# RS232_IrDA.net
KiCad netlist of a schematic drawn in Altium Designer
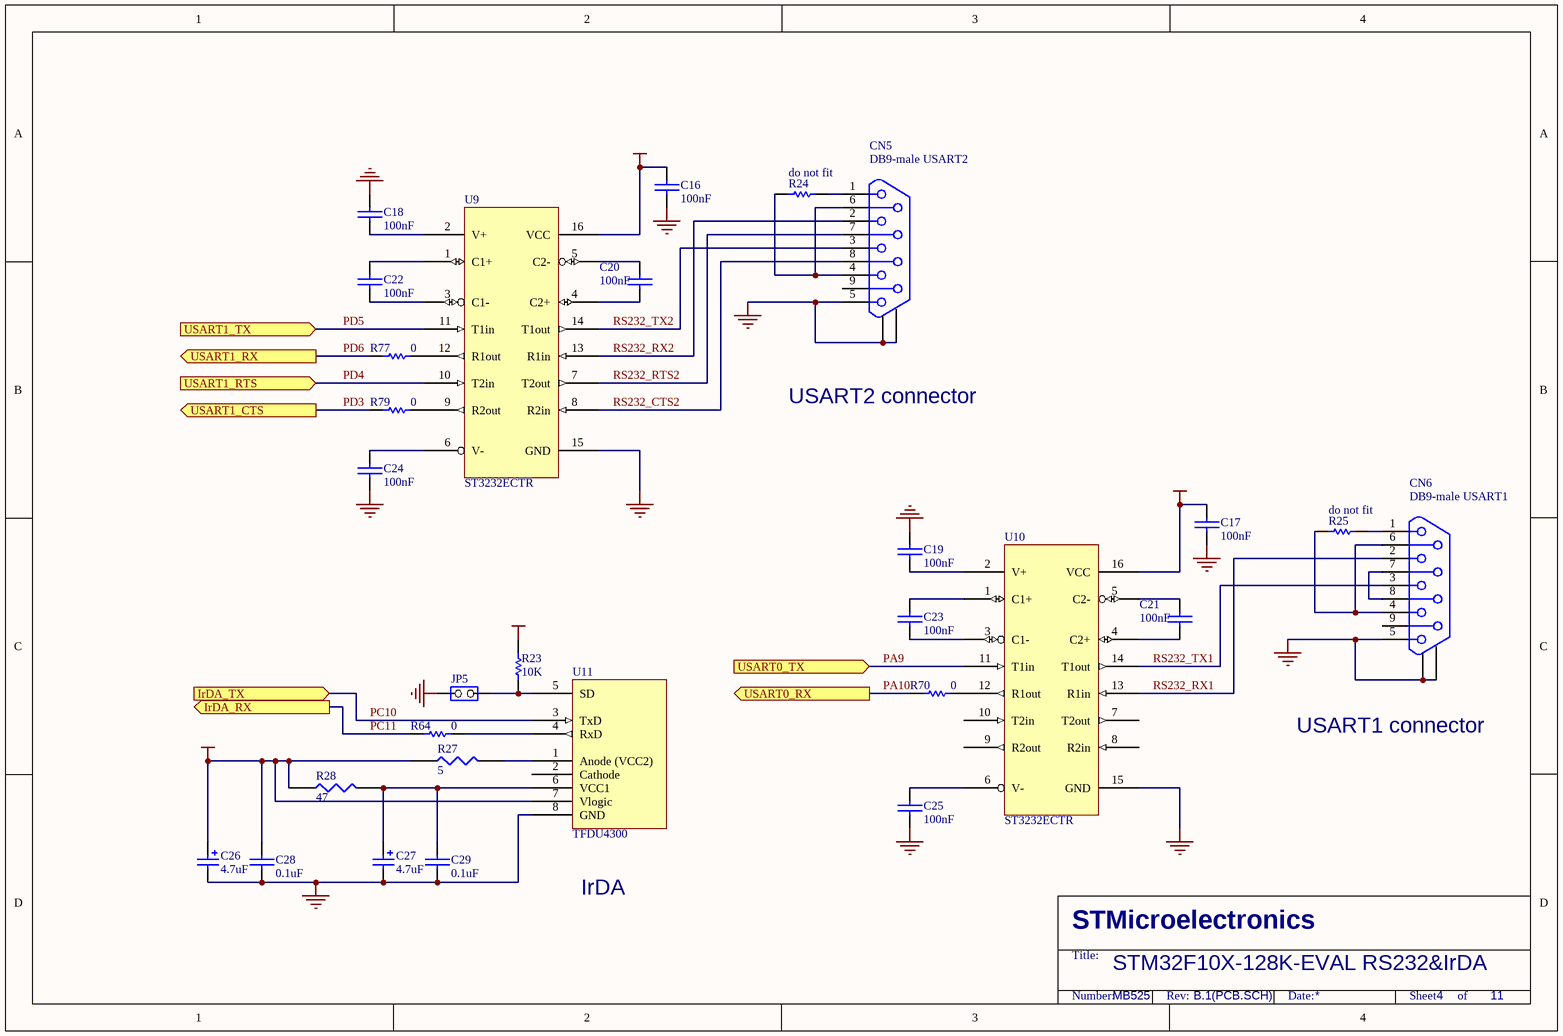
[diagram p0: RS232&IrDA.SchDoc]

(export (version "E")
  (design (tool "Eeschema 10.0.6"))
  (components
    (comp (ref "C16")
      (value "100nF")
      (footprint "0603P")
      (description "Capacitor")
      (libsource (lib "*") (part "CAP"))
    )
    (comp (ref "C17")
      (value "100nF")
      (footprint "0603P")
      (description "Capacitor")
      (libsource (lib "*") (part "CAP"))
    )
    (comp (ref "C18")
      (value "100nF")
      (footprint "0603P")
      (description "Capacitor")
      (libsource (lib "*") (part "CAP"))
    )
    (comp (ref "C19")
      (value "100nF")
      (footprint "0603P")
      (description "Capacitor")
      (libsource (lib "*") (part "CAP"))
    )
    (comp (ref "C20")
      (value "100nF")
      (footprint "0603P")
      (description "Capacitor")
      (libsource (lib "*") (part "CAP"))
    )
    (comp (ref "C21")
      (value "100nF")
      (footprint "0603P")
      (description "Capacitor")
      (libsource (lib "*") (part "CAP"))
    )
    (comp (ref "C22")
      (value "100nF")
      (footprint "0603P")
      (description "Capacitor")
      (libsource (lib "*") (part "CAP"))
    )
    (comp (ref "C23")
      (value "100nF")
      (footprint "0603P")
      (description "Capacitor")
      (libsource (lib "*") (part "CAP"))
    )
    (comp (ref "C24")
      (value "100nF")
      (footprint "0603P")
      (description "Capacitor")
      (libsource (lib "*") (part "CAP"))
    )
    (comp (ref "C25")
      (value "100nF")
      (footprint "0603P")
      (description "Capacitor")
      (libsource (lib "*") (part "CAP"))
    )
    (comp (ref "C26")
      (value "4.7uF")
      (footprint "TAN-B")
      (description "Polarized Capacitor (Radial)")
      (fields (field (name "PUBLISHER") "Altium Limited"))
      (libsource (lib "Miscellaneous Devices") (part "Cap Pol1"))
    )
    (comp (ref "C27")
      (value "4.7uF")
      (footprint "TAN-B")
      (description "Polarized Capacitor (Radial)")
      (fields (field (name "PUBLISHER") "Altium Limited"))
      (libsource (lib "Miscellaneous Devices") (part "Cap Pol1"))
    )
    (comp (ref "C28")
      (value "0.1uF")
      (footprint "0603P")
      (description "Capacitor")
      (libsource (lib "*") (part "CAP"))
    )
    (comp (ref "C29")
      (value "0.1uF")
      (footprint "0603P")
      (description "Capacitor")
      (libsource (lib "*") (part "CAP"))
    )
    (comp (ref "CN5") (value "DB9-male USART2") (footprint "DB9/M") (libsource (lib "*") (part "DB9")))
    (comp (ref "CN6") (value "DB9-male USART1") (footprint "DB9/M") (libsource (lib "*") (part "DB9")))
    (comp (ref "JP5") (value "~") (footprint "SIP2") (libsource (lib "*") (part "JP2")))
    (comp (ref "R23")
      (value "10K")
      (description "Resistor")
      (fields (field (name "PUBLISHER") "Altium Limited"))
      (libsource (lib "Miscellaneous Devices") (part "Res1"))
    )
    (comp (ref "R24")
      (value "do not fit")
      (footprint "0603_NC")
      (description "Resistor")
      (fields (field (name "PUBLISHER") "Altium Limited"))
      (libsource (lib "Miscellaneous Devices") (part "res1"))
    )
    (comp (ref "R25")
      (value "do not fit")
      (footprint "0603_NC")
      (description "Resistor")
      (fields (field (name "PUBLISHER") "Altium Limited"))
      (libsource (lib "Miscellaneous Devices") (part "res1"))
    )
    (comp (ref "R27") (value "5") (footprint "0603") (libsource (lib "*") (part "RES1")))
    (comp (ref "R28") (value "47") (footprint "0603") (libsource (lib "*") (part "RES1")))
    (comp (ref "R64")
      (value "0")
      (description "Resistor")
      (fields (field (name "PUBLISHER") "Altium Limited"))
      (libsource (lib "Miscellaneous Devices") (part "Res1"))
    )
    (comp (ref "R70")
      (value "0")
      (description "Resistor")
      (fields (field (name "PUBLISHER") "Altium Limited"))
      (libsource (lib "Miscellaneous Devices") (part "Res1"))
    )
    (comp (ref "R77")
      (value "0")
      (description "Resistor")
      (fields (field (name "PUBLISHER") "Altium Limited"))
      (libsource (lib "Miscellaneous Devices") (part "Res1"))
    )
    (comp (ref "R79")
      (value "0")
      (description "Resistor")
      (fields (field (name "PUBLISHER") "Altium Limited"))
      (libsource (lib "Miscellaneous Devices") (part "Res1"))
    )
    (comp (ref "U9")
      (value "ST3232ECTR")
      (footprint "TSSOP16")
      (description "3.3V/5V Dual RS232 Transceiver w/ Int. Cap.")
      (libsource (lib "*") (part "ST3232"))
    )
    (comp (ref "U10")
      (value "ST3232ECTR")
      (footprint "TSSOP16")
      (description "3.3V/5V Dual RS232 Transceiver w/ Int. Cap.")
      (libsource (lib "*") (part "ST3232"))
    )
    (comp (ref "U11") (value "TFDU4300") (footprint "IR_VISHAY3") (libsource (lib "*") (part "TFDU4300")))
  )
  (nets
    (net (code "1") (name "+3V3") (class "Default")
      (node (ref "C16") (pin "1") (pinfunction "1_1") (pintype "passive"))
      (node (ref "C17") (pin "1") (pinfunction "1_1") (pintype "passive"))
      (node (ref "C26") (pin "1") (pinfunction "1_1") (pintype "passive"))
      (node (ref "C28") (pin "1") (pinfunction "1_1") (pintype "passive"))
      (node (ref "R23") (pin "2") (pinfunction "2_2") (pintype "passive"))
      (node (ref "R27") (pin "1") (pinfunction "1_1") (pintype "passive"))
      (node (ref "R28") (pin "1") (pinfunction "1_1") (pintype "passive"))
      (node (ref "U10") (pin "16") (pinfunction "VCC_16") (pintype "passive"))
      (node (ref "U11") (pin "7") (pinfunction "Vlogic_7") (pintype "passive"))
      (node (ref "U9") (pin "16") (pinfunction "VCC_16") (pintype "passive"))
    )
    (net (code "2") (name "/PA9") (class "Default")
      (node (ref "U10") (pin "11") (pinfunction "T1in_11") (pintype "input"))
    )
    (net (code "3") (name "/PA10") (class "Default")
      (node (ref "R70") (pin "2") (pinfunction "2_2") (pintype "passive"))
    )
    (net (code "4") (name "/PC10") (class "Default")
      (node (ref "U11") (pin "3") (pinfunction "TxD_3") (pintype "input"))
    )
    (net (code "5") (name "/PC11") (class "Default")
      (node (ref "R64") (pin "2") (pinfunction "2_2") (pintype "passive"))
    )
    (net (code "6") (name "/PD3") (class "Default")
      (node (ref "R79") (pin "2") (pinfunction "2_2") (pintype "passive"))
    )
    (net (code "7") (name "/PD4") (class "Default")
      (node (ref "U9") (pin "10") (pinfunction "T2in_10") (pintype "input"))
    )
    (net (code "8") (name "/PD5") (class "Default")
      (node (ref "U9") (pin "11") (pinfunction "T1in_11") (pintype "input"))
    )
    (net (code "9") (name "/PD6") (class "Default")
      (node (ref "R77") (pin "2") (pinfunction "2_2") (pintype "passive"))
    )
    (net (code "10") (name "/RS232_CTS2") (class "Default")
      (node (ref "CN5") (pin "8") (pinfunction "8_8") (pintype "passive"))
      (node (ref "U9") (pin "8") (pinfunction "R2in_8") (pintype "input"))
    )
    (net (code "11") (name "/RS232_RTS2") (class "Default")
      (node (ref "CN5") (pin "7") (pinfunction "7_7") (pintype "passive"))
      (node (ref "U9") (pin "7") (pinfunction "T2out_7") (pintype "output"))
    )
    (net (code "12") (name "/RS232_RX1") (class "Default")
      (node (ref "CN6") (pin "2") (pinfunction "2_2") (pintype "passive"))
      (node (ref "U10") (pin "13") (pinfunction "R1in_13") (pintype "input"))
    )
    (net (code "13") (name "/RS232_RX2") (class "Default")
      (node (ref "CN5") (pin "2") (pinfunction "2_2") (pintype "passive"))
      (node (ref "U9") (pin "13") (pinfunction "R1in_13") (pintype "input"))
    )
    (net (code "14") (name "/RS232_TX1") (class "Default")
      (node (ref "CN6") (pin "3") (pinfunction "3_3") (pintype "passive"))
      (node (ref "U10") (pin "14") (pinfunction "T1out_14") (pintype "output"))
    )
    (net (code "15") (name "/RS232_TX2") (class "Default")
      (node (ref "CN5") (pin "3") (pinfunction "3_3") (pintype "passive"))
      (node (ref "U9") (pin "14") (pinfunction "T1out_14") (pintype "output"))
    )
    (net (code "16") (name "GND") (class "Default")
      (node (ref "C16") (pin "2") (pinfunction "2_2") (pintype "passive"))
      (node (ref "C17") (pin "2") (pinfunction "2_2") (pintype "passive"))
      (node (ref "C18") (pin "1") (pinfunction "1_1") (pintype "passive"))
      (node (ref "C19") (pin "1") (pinfunction "1_1") (pintype "passive"))
      (node (ref "C24") (pin "1") (pinfunction "1_1") (pintype "passive"))
      (node (ref "C25") (pin "1") (pinfunction "1_1") (pintype "passive"))
      (node (ref "C26") (pin "2") (pinfunction "2_2") (pintype "passive"))
      (node (ref "C27") (pin "2") (pinfunction "2_2") (pintype "passive"))
      (node (ref "C28") (pin "2") (pinfunction "2_2") (pintype "passive"))
      (node (ref "C29") (pin "2") (pinfunction "2_2") (pintype "passive"))
      (node (ref "CN5") (pin "0") (pinfunction "10_0") (pintype "passive"))
      (node (ref "CN5") (pin "5") (pinfunction "5_5") (pintype "passive"))
      (node (ref "CN6") (pin "0") (pinfunction "10_0") (pintype "passive"))
      (node (ref "CN6") (pin "5") (pinfunction "5_5") (pintype "passive"))
      (node (ref "JP5") (pin "2") (pinfunction "NO_2") (pintype "passive"))
      (node (ref "U10") (pin "15") (pinfunction "GND_15") (pintype "passive"))
      (node (ref "U11") (pin "8") (pinfunction "GND_8") (pintype "passive"))
      (node (ref "U9") (pin "15") (pinfunction "GND_15") (pintype "passive"))
    )
    (net (code "17") (name "Net-(CN5-Pad1)") (class "Default")
      (node (ref "CN5") (pin "1") (pinfunction "1_1") (pintype "passive"))
      (node (ref "R24") (pin "2") (pinfunction "2_2") (pintype "passive"))
    )
    (net (code "18") (name "Net-(CN5-Pad4)") (class "Default")
      (node (ref "CN5") (pin "4") (pinfunction "4_4") (pintype "passive"))
      (node (ref "CN5") (pin "6") (pinfunction "6_6") (pintype "passive"))
      (node (ref "R24") (pin "1") (pinfunction "1_1") (pintype "passive"))
    )
    (net (code "19") (name "Net-(CN6-Pad1)") (class "Default")
      (node (ref "CN6") (pin "1") (pinfunction "1_1") (pintype "passive"))
      (node (ref "R25") (pin "2") (pinfunction "2_2") (pintype "passive"))
    )
    (net (code "20") (name "Net-(CN6-Pad4)") (class "Default")
      (node (ref "CN6") (pin "4") (pinfunction "4_4") (pintype "passive"))
      (node (ref "CN6") (pin "6") (pinfunction "6_6") (pintype "passive"))
      (node (ref "R25") (pin "1") (pinfunction "1_1") (pintype "passive"))
    )
    (net (code "21") (name "Net-(CN6-Pad7)") (class "Default")
      (node (ref "CN6") (pin "7") (pinfunction "7_7") (pintype "passive"))
      (node (ref "CN6") (pin "8") (pinfunction "8_8") (pintype "passive"))
    )
    (net (code "22") (name "Net-(JP5-COMMON)") (class "Default")
      (node (ref "JP5") (pin "1") (pinfunction "COMMON_1") (pintype "passive"))
      (node (ref "R23") (pin "1") (pinfunction "1_1") (pintype "passive"))
      (node (ref "U11") (pin "5") (pinfunction "SD_5") (pintype "passive"))
    )
    (net (code "23") (name "Net-(U9-C1+)") (class "Default")
      (node (ref "C22") (pin "1") (pinfunction "1_1") (pintype "passive"))
      (node (ref "U9") (pin "1") (pinfunction "C1+_1") (pintype "bidirectional"))
    )
    (net (code "24") (name "Net-(U9-C1-)") (class "Default")
      (node (ref "C22") (pin "2") (pinfunction "2_2") (pintype "passive"))
      (node (ref "U9") (pin "3") (pinfunction "C1-_3") (pintype "bidirectional"))
    )
    (net (code "25") (name "Net-(U9-C2+)") (class "Default")
      (node (ref "C20") (pin "1") (pinfunction "1_1") (pintype "passive"))
      (node (ref "U9") (pin "4") (pinfunction "C2+_4") (pintype "bidirectional"))
    )
    (net (code "26") (name "Net-(U9-C2-)") (class "Default")
      (node (ref "C20") (pin "2") (pinfunction "2_2") (pintype "passive"))
      (node (ref "U9") (pin "5") (pinfunction "C2-_5") (pintype "bidirectional"))
    )
    (net (code "27") (name "Net-(U9-R1out)") (class "Default")
      (node (ref "R77") (pin "1") (pinfunction "1_1") (pintype "passive"))
      (node (ref "U9") (pin "12") (pinfunction "R1out_12") (pintype "output"))
    )
    (net (code "28") (name "Net-(U9-R2out)") (class "Default")
      (node (ref "R79") (pin "1") (pinfunction "1_1") (pintype "passive"))
      (node (ref "U9") (pin "9") (pinfunction "R2out_9") (pintype "output"))
    )
    (net (code "29") (name "Net-(U9-V+)") (class "Default")
      (node (ref "C18") (pin "2") (pinfunction "2_2") (pintype "passive"))
      (node (ref "U9") (pin "2") (pinfunction "V+_2") (pintype "passive"))
    )
    (net (code "30") (name "Net-(U9-V-)") (class "Default")
      (node (ref "C24") (pin "2") (pinfunction "2_2") (pintype "passive"))
      (node (ref "U9") (pin "6") (pinfunction "V-_6") (pintype "passive"))
    )
    (net (code "31") (name "Net-(U10-C1+)") (class "Default")
      (node (ref "C23") (pin "1") (pinfunction "1_1") (pintype "passive"))
      (node (ref "U10") (pin "1") (pinfunction "C1+_1") (pintype "bidirectional"))
    )
    (net (code "32") (name "Net-(U10-C1-)") (class "Default")
      (node (ref "C23") (pin "2") (pinfunction "2_2") (pintype "passive"))
      (node (ref "U10") (pin "3") (pinfunction "C1-_3") (pintype "bidirectional"))
    )
    (net (code "33") (name "Net-(U10-C2+)") (class "Default")
      (node (ref "C21") (pin "1") (pinfunction "1_1") (pintype "passive"))
      (node (ref "U10") (pin "4") (pinfunction "C2+_4") (pintype "bidirectional"))
    )
    (net (code "34") (name "Net-(U10-C2-)") (class "Default")
      (node (ref "C21") (pin "2") (pinfunction "2_2") (pintype "passive"))
      (node (ref "U10") (pin "5") (pinfunction "C2-_5") (pintype "bidirectional"))
    )
    (net (code "35") (name "Net-(U10-R1out)") (class "Default")
      (node (ref "R70") (pin "1") (pinfunction "1_1") (pintype "passive"))
      (node (ref "U10") (pin "12") (pinfunction "R1out_12") (pintype "output"))
    )
    (net (code "36") (name "Net-(U10-V+)") (class "Default")
      (node (ref "C19") (pin "2") (pinfunction "2_2") (pintype "passive"))
      (node (ref "U10") (pin "2") (pinfunction "V+_2") (pintype "passive"))
    )
    (net (code "37") (name "Net-(U10-V-)") (class "Default")
      (node (ref "C25") (pin "2") (pinfunction "2_2") (pintype "passive"))
      (node (ref "U10") (pin "6") (pinfunction "V-_6") (pintype "passive"))
    )
    (net (code "38") (name "Net-(U11-Anode_(VCC2))") (class "Default")
      (node (ref "R27") (pin "2") (pinfunction "2_2") (pintype "passive"))
      (node (ref "U11") (pin "1") (pinfunction "Anode_(VCC2)_1") (pintype "passive"))
    )
    (net (code "39") (name "Net-(U11-RxD)") (class "Default")
      (node (ref "R64") (pin "1") (pinfunction "1_1") (pintype "passive"))
      (node (ref "U11") (pin "4") (pinfunction "RxD_4") (pintype "output"))
    )
    (net (code "40") (name "Net-(U11-VCC1)") (class "Default")
      (node (ref "C27") (pin "1") (pinfunction "1_1") (pintype "passive"))
      (node (ref "C29") (pin "1") (pinfunction "1_1") (pintype "passive"))
      (node (ref "R28") (pin "2") (pinfunction "2_2") (pintype "passive"))
      (node (ref "U11") (pin "6") (pinfunction "VCC1_6") (pintype "passive"))
    )
    (net (code "41") (name "unconnected-(CN5-Pad9)") (class "Default")
      (node (ref "CN5") (pin "9") (pinfunction "9_9") (pintype "passive"))
    )
    (net (code "42") (name "unconnected-(CN6-Pad9)") (class "Default")
      (node (ref "CN6") (pin "9") (pinfunction "9_9") (pintype "passive"))
    )
    (net (code "43") (name "unconnected-(U10-R2in-Pad8)") (class "Default")
      (node (ref "U10") (pin "8") (pinfunction "R2in_8") (pintype "input"))
    )
    (net (code "44") (name "unconnected-(U10-R2out-Pad9)") (class "Default")
      (node (ref "U10") (pin "9") (pinfunction "R2out_9") (pintype "output"))
    )
    (net (code "45") (name "unconnected-(U10-T2in-Pad10)") (class "Default")
      (node (ref "U10") (pin "10") (pinfunction "T2in_10") (pintype "input"))
    )
    (net (code "46") (name "unconnected-(U10-T2out-Pad7)") (class "Default")
      (node (ref "U10") (pin "7") (pinfunction "T2out_7") (pintype "output"))
    )
    (net (code "47") (name "unconnected-(U11-Cathode-Pad2)") (class "Default")
      (node (ref "U11") (pin "2") (pinfunction "Cathode_2") (pintype "passive"))
    )
  )
)
